# chuck_rev_2.net
KiCad netlist of a schematic drawn in EAGLE
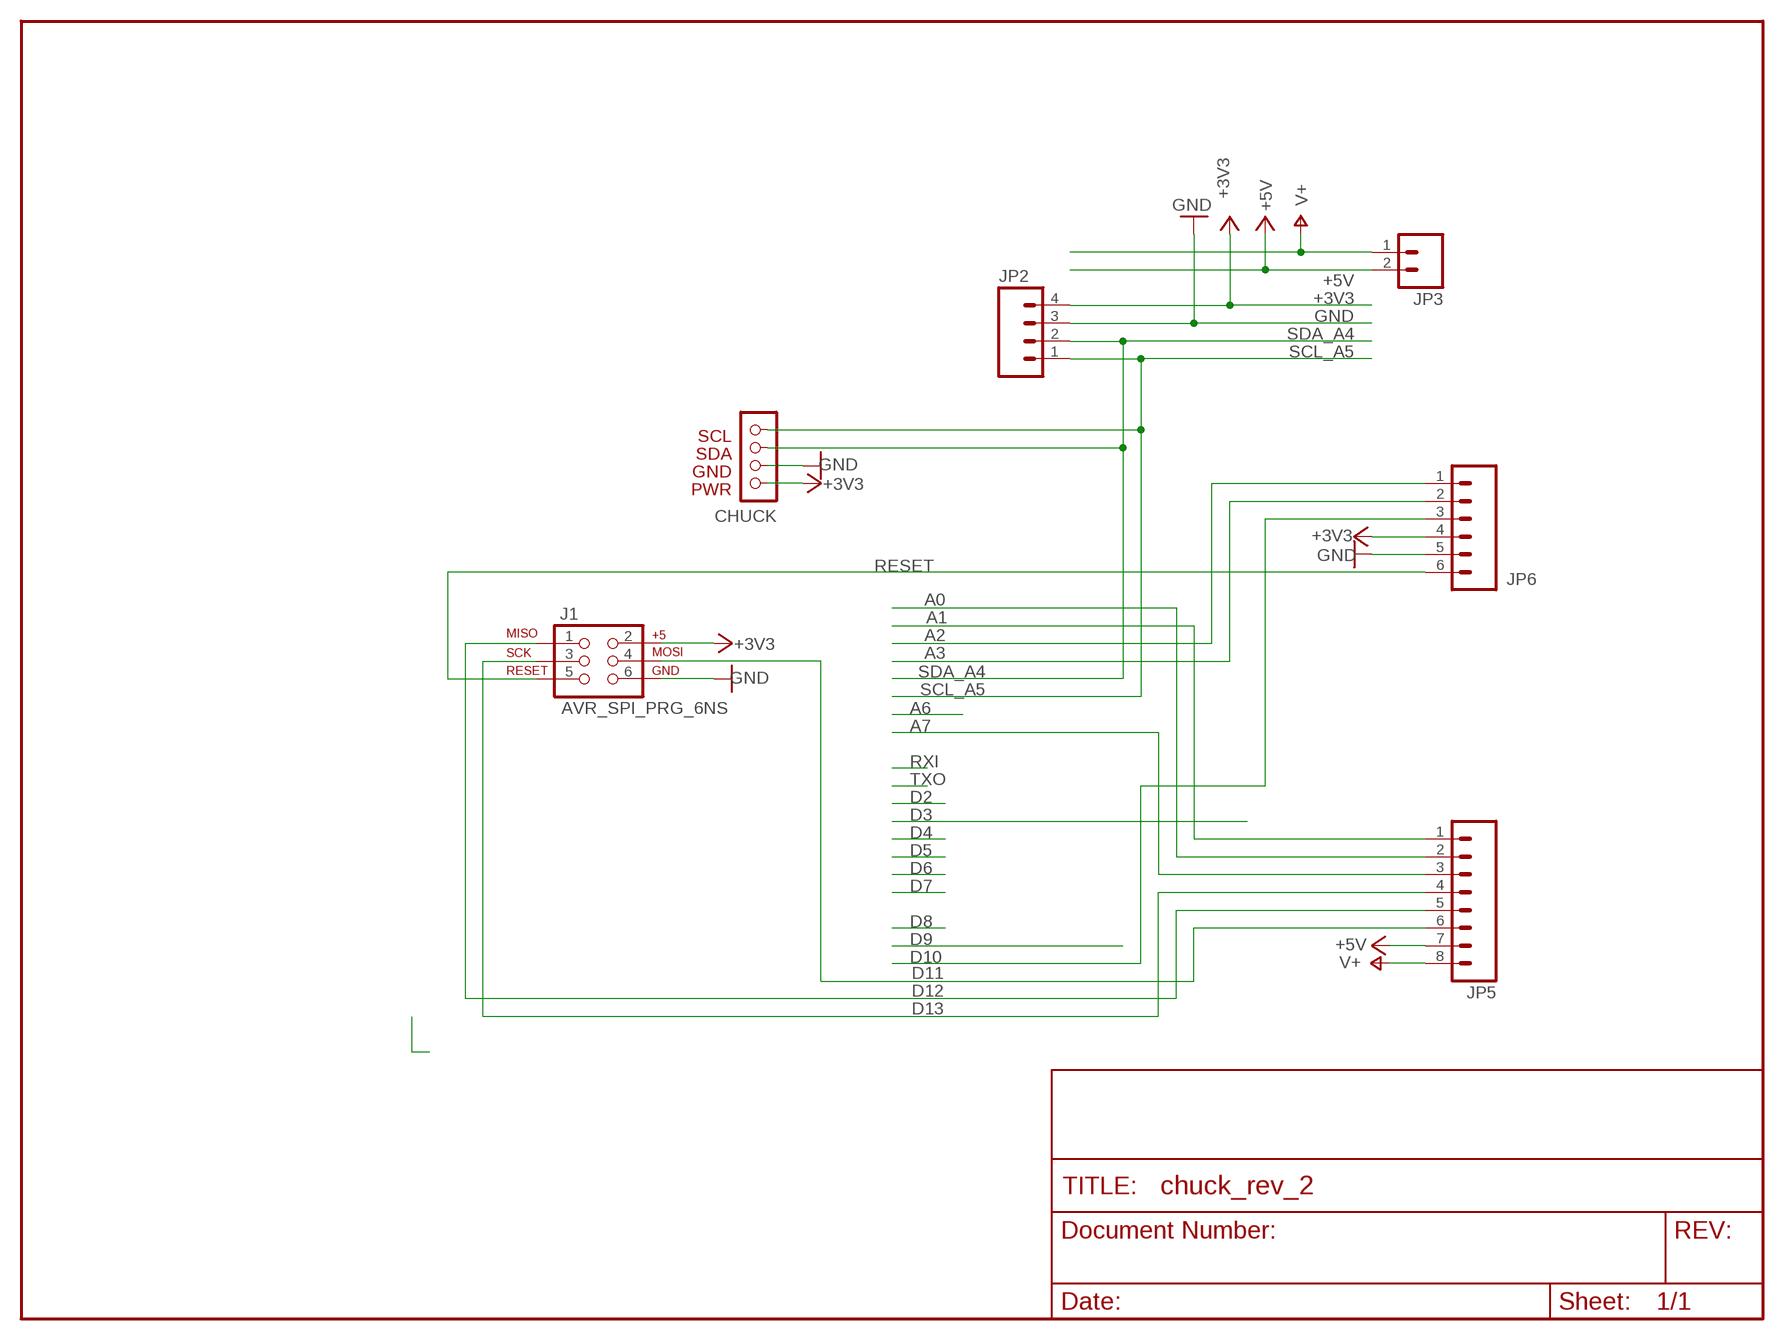
[diagram p0: schematic, sheet 1]

(export (version "E")
  (design (tool "Eeschema 10.0.6"))
  (components
    (comp (ref "CHUCK")
      (value "NUNCHUCK")
      (footprint "eagle-import:CONN")
      (libsource (lib "eagle-import") (part "NUNCHUCK"))
    )
    (comp (ref "J1")
      (value "AVR_SPI_PRG_6NS")
      (footprint "eagle-import:2X3-NS")
      (libsource (lib "eagle-import") (part "AVR_SPI_PRG_6NS"))
    )
    (comp (ref "JP2")
      (value "M04PTH")
      (footprint "eagle-import:1X04")
      (libsource (lib "eagle-import") (part "M04PTH"))
    )
    (comp (ref "JP3")
      (value "M02PTH")
      (footprint "eagle-import:1X02")
      (libsource (lib "eagle-import") (part "M02PTH"))
    )
    (comp (ref "JP5")
      (value "M081X08")
      (footprint "eagle-import:1X08")
      (libsource (lib "eagle-import") (part "M081X08"))
    )
    (comp (ref "JP6")
      (value "M06SIP")
      (footprint "eagle-import:1X06")
      (libsource (lib "eagle-import") (part "M06SIP"))
    )
  )
  (nets
    (net (code "1") (name "+3V3") (class "Default")
      (node (ref "CHUCK") (pin "PWR") (pinfunction "PWR_PWR") (pintype "power_in"))
      (node (ref "J1") (pin "2") (pinfunction "2_2") (pintype "passive"))
      (node (ref "JP2") (pin "4") (pinfunction "4_4") (pintype "passive"))
      (node (ref "JP6") (pin "4") (pinfunction "4_4") (pintype "passive"))
    )
    (net (code "2") (name "+5V") (class "Default")
      (node (ref "JP3") (pin "2") (pinfunction "2_2") (pintype "passive"))
      (node (ref "JP5") (pin "7") (pinfunction "7_7") (pintype "passive"))
    )
    (net (code "3") (name "/A0") (class "Default")
      (node (ref "JP5") (pin "2") (pinfunction "2_2") (pintype "passive"))
    )
    (net (code "4") (name "/A1") (class "Default")
      (node (ref "JP5") (pin "1") (pinfunction "1_1") (pintype "passive"))
    )
    (net (code "5") (name "/A2") (class "Default")
      (node (ref "JP6") (pin "1") (pinfunction "1_1") (pintype "passive"))
    )
    (net (code "6") (name "/A3") (class "Default")
      (node (ref "JP6") (pin "2") (pinfunction "2_2") (pintype "passive"))
    )
    (net (code "8") (name "/A7") (class "Default")
      (node (ref "JP5") (pin "3") (pinfunction "3_3") (pintype "passive"))
    )
    (net (code "17") (name "/D10") (class "Default")
      (node (ref "JP6") (pin "3") (pinfunction "3_3") (pintype "passive"))
    )
    (net (code "18") (name "/D11") (class "Default")
      (node (ref "J1") (pin "4") (pinfunction "4_4") (pintype "passive"))
      (node (ref "JP5") (pin "6") (pinfunction "6_6") (pintype "passive"))
    )
    (net (code "19") (name "/D12") (class "Default")
      (node (ref "J1") (pin "1") (pinfunction "1_1") (pintype "passive"))
      (node (ref "JP5") (pin "5") (pinfunction "5_5") (pintype "passive"))
    )
    (net (code "20") (name "/D13") (class "Default")
      (node (ref "J1") (pin "3") (pinfunction "3_3") (pintype "passive"))
      (node (ref "JP5") (pin "4") (pinfunction "4_4") (pintype "passive"))
    )
    (net (code "21") (name "/RESET") (class "Default")
      (node (ref "J1") (pin "5") (pinfunction "5_5") (pintype "passive"))
      (node (ref "JP6") (pin "6") (pinfunction "6_6") (pintype "passive"))
    )
    (net (code "23") (name "/SCL_A5") (class "Default")
      (node (ref "CHUCK") (pin "SCL") (pinfunction "SCL_SCL") (pintype "bidirectional"))
      (node (ref "JP2") (pin "1") (pinfunction "1_1") (pintype "passive"))
    )
    (net (code "24") (name "/SDA_A4") (class "Default")
      (node (ref "CHUCK") (pin "SDA") (pinfunction "SDA_SDA") (pintype "bidirectional"))
      (node (ref "JP2") (pin "2") (pinfunction "2_2") (pintype "passive"))
    )
    (net (code "26") (name "GND") (class "Default")
      (node (ref "CHUCK") (pin "GND") (pinfunction "GND_GND") (pintype "passive"))
      (node (ref "J1") (pin "6") (pinfunction "6_6") (pintype "passive"))
      (node (ref "JP2") (pin "3") (pinfunction "3_3") (pintype "passive"))
      (node (ref "JP6") (pin "5") (pinfunction "5_5") (pintype "passive"))
    )
    (net (code "27") (name "V+") (class "Default")
      (node (ref "JP3") (pin "1") (pinfunction "1_1") (pintype "passive"))
      (node (ref "JP5") (pin "8") (pinfunction "8_8") (pintype "passive"))
    )
  )
)
